# LCD-43.net
KiCad netlist of a schematic drawn in Altium Designer
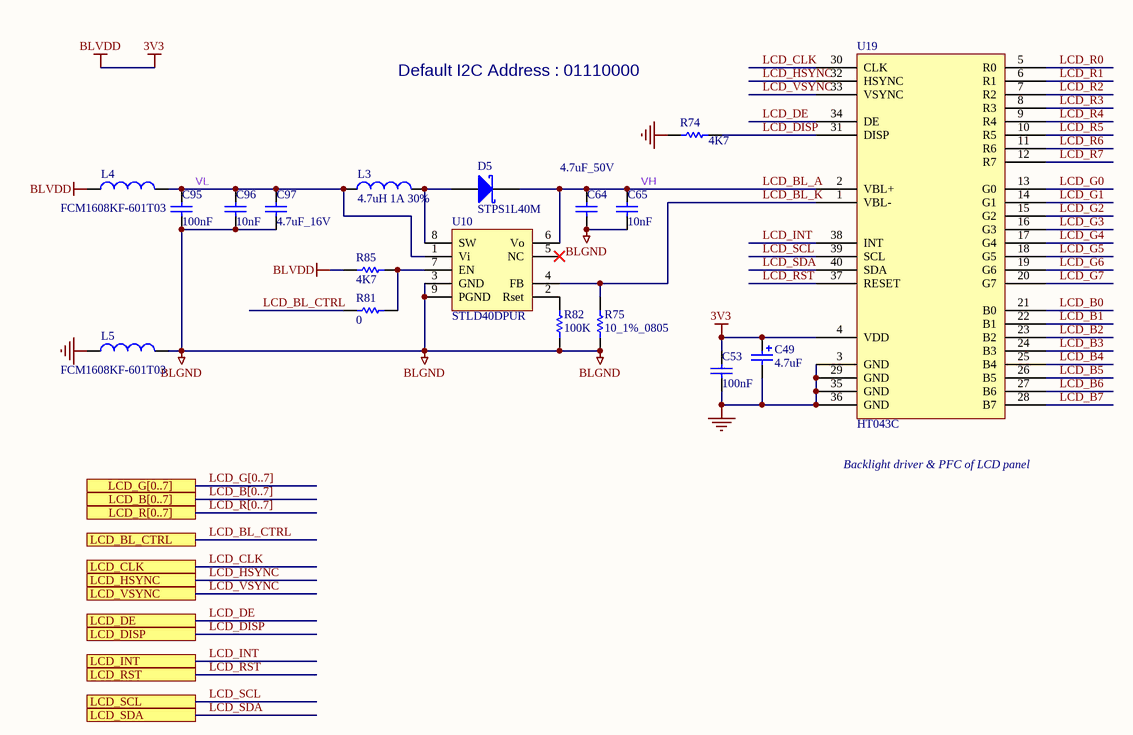
[diagram p0: LCD-43.SchDoc]

(export (version "E")
  (design (tool "Eeschema 10.0.6"))
  (components
    (comp (ref "C49")
      (value "4.7uF")
      (footprint "TAN-A")
      (description "Polarized Capacitor,4.7uF,16V,10%,typeA,AVX")
      (libsource (lib "MCD_TOOLS") (part "Cap_4.7uF_POL_10%_TANA"))
    )
    (comp (ref "C53")
      (value "100nF")
      (footprint "0402C")
      (description "Capacitor,100nF,16V,X7R,10%,0402,YAGEO")
      (libsource (lib "MCD_TOOLS") (part "Cap_100nF_X7R_10%_0402"))
    )
    (comp (ref "C64")
      (value "4.7uF_50V")
      (footprint "1206C")
      (description "Capacitor,4.7uF,50V, X7R,10%,1206,AVX")
      (libsource (lib "MCD_TOOLS") (part "Cap_4.7uF_X7R_10%_1206"))
    )
    (comp (ref "C65")
      (value "10nF")
      (footprint "0603C")
      (description "Capacitor,10nF,50V,X7R,10%,0603,YAGEO")
      (libsource (lib "MCD_TOOLS") (part "Cap_10nF_X7R_10%_0603"))
    )
    (comp (ref "C95")
      (value "100nF")
      (footprint "0603C")
      (description "Capacitor,100nF,16V,X7R,10%,0603,YAGEO")
      (libsource (lib "MCD_TOOLS") (part "Cap_100nF_X7R_10%_0603"))
    )
    (comp (ref "C96")
      (value "10nF")
      (footprint "0603C")
      (description "Capacitor,10nF,50V,X7R,10%,0603,YAGEO")
      (libsource (lib "MCD_TOOLS") (part "Cap_10nF_X7R_10%_0603"))
    )
    (comp (ref "C97")
      (value "4.7uF_16V")
      (footprint "1206C")
      (description "Capacitor,4.7uF,16V, X5R,10%,1206,AVX")
      (libsource (lib "MCD_TOOLS") (part "Cap_4.7uF_X5R_10%_1206"))
    )
    (comp (ref "D5")
      (value "STPS1L40M")
      (footprint "DO216-AA")
      (description "Low Drop power Schottky rectifier(1A, 40V, 0.4V)")
      (libsource (lib "MCD_TOOLS") (part "STPS1L40M"))
    )
    (comp (ref "L3")
      (value "4.7uH 1A 30%")
      (footprint "1210L")
      (description "FIXED IND 4.7UH 1A 180 MOHM 30% SMD")
      (libsource (lib "MCD_TOOLS") (part "Ind_4.7uH_1A_30%"))
    )
    (comp (ref "L4")
      (value "FCM1608KF-601T03")
      (footprint "0603L")
      (description "Bead,600R,350mA,0603,FCM1608KF-601T03,Tai-tech")
      (libsource (lib "MCD_TOOLS") (part "BEAD_600R_350MA_0603"))
    )
    (comp (ref "L5")
      (value "FCM1608KF-601T03")
      (footprint "0603L")
      (description "Bead,600R,350mA,0603,FCM1608KF-601T03,Tai-tech")
      (libsource (lib "MCD_TOOLS") (part "BEAD_600R_350MA_0603"))
    )
    (comp (ref "R74")
      (value "4K7")
      (footprint "0402R")
      (description "Resistor,4K7,0402,1%,YAGEO")
      (libsource (lib "MCD_TOOLS") (part "Res_4K7_1%_0402"))
    )
    (comp (ref "R75")
      (value "10_1%_0805")
      (footprint "0805R")
      (description "Resistor,10,0805,1%,Stackpole,1/4W")
      (libsource (lib "MCD_TOOLS") (part "Res_10_1%_0805"))
    )
    (comp (ref "R81")
      (value "0")
      (footprint "0402R")
      (description "Resistor,0,0402,5%,YAGEO")
      (libsource (lib "MCD_TOOLS") (part "Res_0_5%_0402"))
    )
    (comp (ref "R82")
      (value "100K")
      (footprint "0402R")
      (description "Resistor,100K,0402,1%,YAGEO")
      (libsource (lib "MCD_TOOLS") (part "Res_100K_1%_0402"))
    )
    (comp (ref "R85")
      (value "4K7")
      (footprint "0402R")
      (description "Resistor,4K7,0402,1%,YAGEO")
      (libsource (lib "MCD_TOOLS") (part "Res_4K7_1%_0402"))
    )
    (comp (ref "U10")
      (value "STLD40DPUR")
      (footprint "QFN8_0R65_3X3_ST")
      (description "White LED power supply for large display backlight, QFN8")
      (libsource (lib "MCD_TOOLS") (part "STLD40DPUR"))
    )
    (comp (ref "U19")
      (value "HT043C")
      (footprint "LCD_Kunjian_ HT043C_40P_P080_FLEX_FOLDED")
      (description "4.3 inch TFT 480*272 pixels with LED Backlight and Capacitive touch panel, high luminance")
      (libsource (lib "Mb1191") (part "HT043C"))
    )
  )
  (nets
    (net (code "1") (name "/LCD_B0") (class "Default")
      (node (ref "U19") (pin "21") (pinfunction "B0_21") (pintype "passive"))
    )
    (net (code "2") (name "/LCD_B1") (class "Default")
      (node (ref "U19") (pin "22") (pinfunction "B1_22") (pintype "passive"))
    )
    (net (code "3") (name "/LCD_B2") (class "Default")
      (node (ref "U19") (pin "23") (pinfunction "B2_23") (pintype "passive"))
    )
    (net (code "4") (name "/LCD_B3") (class "Default")
      (node (ref "U19") (pin "24") (pinfunction "B3_24") (pintype "passive"))
    )
    (net (code "5") (name "/LCD_B4") (class "Default")
      (node (ref "U19") (pin "25") (pinfunction "B4_25") (pintype "passive"))
    )
    (net (code "6") (name "/LCD_B5") (class "Default")
      (node (ref "U19") (pin "26") (pinfunction "B5_26") (pintype "passive"))
    )
    (net (code "7") (name "/LCD_B6") (class "Default")
      (node (ref "U19") (pin "27") (pinfunction "B6_27") (pintype "passive"))
    )
    (net (code "8") (name "/LCD_B7") (class "Default")
      (node (ref "U19") (pin "28") (pinfunction "B7_28") (pintype "passive"))
    )
    (net (code "9") (name "/LCD_BL_A") (class "Default")
      (node (ref "C64") (pin "1") (pinfunction "1_1") (pintype "passive"))
      (node (ref "C65") (pin "2") (pinfunction "2_2") (pintype "passive"))
      (node (ref "D5") (pin "2") (pinfunction "K_2") (pintype "passive"))
      (node (ref "U10") (pin "6") (pinfunction "Vo_6") (pintype "passive"))
      (node (ref "U19") (pin "2") (pinfunction "VBL+_2") (pintype "passive"))
    )
    (net (code "10") (name "/LCD_BL_CTRL") (class "Default")
      (node (ref "R81") (pin "2") (pinfunction "2_2") (pintype "passive"))
    )
    (net (code "11") (name "/LCD_BL_K") (class "Default")
      (node (ref "R75") (pin "2") (pinfunction "2_2") (pintype "passive"))
      (node (ref "U10") (pin "4") (pinfunction "FB_4") (pintype "passive"))
      (node (ref "U19") (pin "1") (pinfunction "VBL-_1") (pintype "passive"))
    )
    (net (code "13") (name "/LCD_CLK") (class "Default")
      (node (ref "U19") (pin "30") (pinfunction "CLK_30") (pintype "passive"))
    )
    (net (code "14") (name "/LCD_DE") (class "Default")
      (node (ref "U19") (pin "34") (pinfunction "DE_34") (pintype "passive"))
    )
    (net (code "15") (name "/LCD_DISP") (class "Default")
      (node (ref "R74") (pin "1") (pinfunction "1_1") (pintype "passive"))
      (node (ref "U19") (pin "31") (pinfunction "DISP_31") (pintype "passive"))
    )
    (net (code "16") (name "/LCD_G0") (class "Default")
      (node (ref "U19") (pin "13") (pinfunction "G0_13") (pintype "passive"))
    )
    (net (code "17") (name "/LCD_G1") (class "Default")
      (node (ref "U19") (pin "14") (pinfunction "G1_14") (pintype "passive"))
    )
    (net (code "18") (name "/LCD_G2") (class "Default")
      (node (ref "U19") (pin "15") (pinfunction "G2_15") (pintype "passive"))
    )
    (net (code "19") (name "/LCD_G3") (class "Default")
      (node (ref "U19") (pin "16") (pinfunction "G3_16") (pintype "passive"))
    )
    (net (code "20") (name "/LCD_G4") (class "Default")
      (node (ref "U19") (pin "17") (pinfunction "G4_17") (pintype "passive"))
    )
    (net (code "21") (name "/LCD_G5") (class "Default")
      (node (ref "U19") (pin "18") (pinfunction "G5_18") (pintype "passive"))
    )
    (net (code "22") (name "/LCD_G6") (class "Default")
      (node (ref "U19") (pin "19") (pinfunction "G6_19") (pintype "passive"))
    )
    (net (code "23") (name "/LCD_G7") (class "Default")
      (node (ref "U19") (pin "20") (pinfunction "G7_20") (pintype "passive"))
    )
    (net (code "25") (name "/LCD_HSYNC") (class "Default")
      (node (ref "U19") (pin "32") (pinfunction "HSYNC_32") (pintype "passive"))
    )
    (net (code "26") (name "/LCD_INT") (class "Default")
      (node (ref "U19") (pin "38") (pinfunction "INT_38") (pintype "passive"))
    )
    (net (code "27") (name "/LCD_R0") (class "Default")
      (node (ref "U19") (pin "5") (pinfunction "R0_5") (pintype "passive"))
    )
    (net (code "28") (name "/LCD_R1") (class "Default")
      (node (ref "U19") (pin "6") (pinfunction "R1_6") (pintype "passive"))
    )
    (net (code "29") (name "/LCD_R2") (class "Default")
      (node (ref "U19") (pin "7") (pinfunction "R2_7") (pintype "passive"))
    )
    (net (code "30") (name "/LCD_R3") (class "Default")
      (node (ref "U19") (pin "8") (pinfunction "R3_8") (pintype "passive"))
    )
    (net (code "31") (name "/LCD_R4") (class "Default")
      (node (ref "U19") (pin "9") (pinfunction "R4_9") (pintype "passive"))
    )
    (net (code "32") (name "/LCD_R5") (class "Default")
      (node (ref "U19") (pin "10") (pinfunction "R5_10") (pintype "passive"))
    )
    (net (code "33") (name "/LCD_R6") (class "Default")
      (node (ref "U19") (pin "11") (pinfunction "R6_11") (pintype "passive"))
    )
    (net (code "34") (name "/LCD_R7") (class "Default")
      (node (ref "U19") (pin "12") (pinfunction "R7_12") (pintype "passive"))
    )
    (net (code "35") (name "/LCD_RST") (class "Default")
      (node (ref "U19") (pin "37") (pinfunction "RESET_37") (pintype "passive"))
    )
    (net (code "37") (name "/LCD_SCL") (class "Default")
      (node (ref "U19") (pin "39") (pinfunction "SCL_39") (pintype "passive"))
    )
    (net (code "38") (name "/LCD_SDA") (class "Default")
      (node (ref "U19") (pin "40") (pinfunction "SDA_40") (pintype "passive"))
    )
    (net (code "39") (name "/LCD_VSYNC") (class "Default")
      (node (ref "U19") (pin "33") (pinfunction "VSYNC_33") (pintype "passive"))
    )
    (net (code "40") (name "/VL") (class "Default")
      (node (ref "C95") (pin "2") (pinfunction "2_2") (pintype "passive"))
      (node (ref "C96") (pin "2") (pinfunction "2_2") (pintype "passive"))
      (node (ref "C97") (pin "1") (pinfunction "1_1") (pintype "passive"))
      (node (ref "L3") (pin "1") (pinfunction "1_1") (pintype "passive"))
      (node (ref "L4") (pin "2") (pinfunction "2_2") (pintype "passive"))
      (node (ref "U10") (pin "1") (pinfunction "Vi_1") (pintype "passive"))
    )
    (net (code "41") (name "3V3") (class "Default")
      (node (ref "C49") (pin "1") (pinfunction "1_1") (pintype "passive"))
      (node (ref "C53") (pin "2") (pinfunction "2_2") (pintype "passive"))
      (node (ref "L4") (pin "1") (pinfunction "1_1") (pintype "passive"))
      (node (ref "R85") (pin "2") (pinfunction "2_2") (pintype "passive"))
      (node (ref "U19") (pin "4") (pinfunction "VDD_4") (pintype "passive"))
    )
    (net (code "42") (name "BLGND") (class "Default")
      (node (ref "C64") (pin "2") (pinfunction "2_2") (pintype "passive"))
      (node (ref "C65") (pin "1") (pinfunction "1_1") (pintype "passive"))
      (node (ref "C95") (pin "1") (pinfunction "1_1") (pintype "passive"))
      (node (ref "C96") (pin "1") (pinfunction "1_1") (pintype "passive"))
      (node (ref "C97") (pin "2") (pinfunction "2_2") (pintype "passive"))
      (node (ref "L5") (pin "2") (pinfunction "2_2") (pintype "passive"))
      (node (ref "R75") (pin "1") (pinfunction "1_1") (pintype "passive"))
      (node (ref "R82") (pin "2") (pinfunction "2_2") (pintype "passive"))
      (node (ref "U10") (pin "3") (pinfunction "GND_3") (pintype "passive"))
      (node (ref "U10") (pin "9") (pinfunction "PGND_9") (pintype "passive"))
    )
    (net (code "43") (name "GND") (class "Default")
      (node (ref "C49") (pin "2") (pinfunction "2_2") (pintype "passive"))
      (node (ref "C53") (pin "1") (pinfunction "1_1") (pintype "passive"))
      (node (ref "L5") (pin "1") (pinfunction "1_1") (pintype "passive"))
      (node (ref "R74") (pin "2") (pinfunction "2_2") (pintype "passive"))
      (node (ref "U19") (pin "29") (pinfunction "GND_29") (pintype "passive"))
      (node (ref "U19") (pin "3") (pinfunction "GND_3") (pintype "passive"))
      (node (ref "U19") (pin "35") (pinfunction "GND_35") (pintype "passive"))
      (node (ref "U19") (pin "36") (pinfunction "GND_36") (pintype "passive"))
    )
    (net (code "44") (name "Net-(D5-A)") (class "Default")
      (node (ref "D5") (pin "1") (pinfunction "A_1") (pintype "passive"))
      (node (ref "L3") (pin "2") (pinfunction "2_2") (pintype "passive"))
      (node (ref "U10") (pin "8") (pinfunction "SW_8") (pintype "passive"))
    )
    (net (code "45") (name "Net-(U10-EN)") (class "Default")
      (node (ref "R81") (pin "1") (pinfunction "1_1") (pintype "passive"))
      (node (ref "R85") (pin "1") (pinfunction "1_1") (pintype "passive"))
      (node (ref "U10") (pin "7") (pinfunction "EN_7") (pintype "passive"))
    )
    (net (code "46") (name "Net-(U10-Rset)") (class "Default")
      (node (ref "R82") (pin "1") (pinfunction "1_1") (pintype "passive"))
      (node (ref "U10") (pin "2") (pinfunction "Rset_2") (pintype "passive"))
    )
    (net (code "47") (name "unconnected-(U10-NC-Pad5)") (class "Default")
      (node (ref "U10") (pin "5") (pinfunction "NC_5") (pintype "passive+no_connect"))
    )
  )
)
